# VOLTAJE.net
KiCad netlist of a schematic drawn in Altium Designer
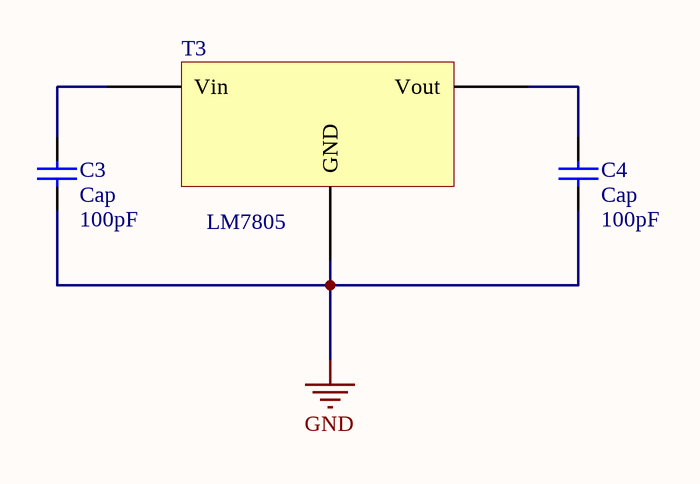
[diagram p0: VOLTAJE.SchDoc]

(export (version "E")
  (design (tool "Eeschema 10.0.6"))
  (components
    (comp (ref "C3")
      (value "Cap")
      (footprint "RAD-0.3")
      (description "Capacitor Ceramico")
      (fields
        (field (name "MANUFACTURER") "KEMET")
        (field (name "MANUFACTURER PART NUMBER") "C0402C104K8PACTU")
        (field (name "ALTIUM_VALUE") "100pF")
        (field (name "PUBLISHER") "Altium Limited")
      )
      (libsource (lib "LIBRERIAPROYECTO") (part "Cap"))
    )
    (comp (ref "C4")
      (value "Cap")
      (footprint "RAD-0.3")
      (description "Capacitor Ceramico")
      (fields
        (field (name "MANUFACTURER") "KEMET")
        (field (name "MANUFACTURER PART NUMBER") "C0402C104K8PACTU")
        (field (name "ALTIUM_VALUE") "100pF")
        (field (name "PUBLISHER") "Altium Limited")
      )
      (libsource (lib "LIBRERIAPROYECTO") (part "Cap"))
    )
    (comp (ref "T3")
      (value "LM7805")
      (footprint "LM7805")
      (description "Voltage Regulator")
      (fields
        (field (name "MANUFACTURER") "ON Semiconductor / Fairchild")
        (field (name "MANUFACTURER PART NUMBER") "LM7805CT")
      )
      (libsource (lib "LIBRERIAPROYECTO") (part "LM7805"))
    )
  )
  (nets
    (net (code "1") (name "GND") (class "Default")
      (node (ref "C3") (pin "1") (pinfunction "1_1") (pintype "passive"))
      (node (ref "C4") (pin "1") (pinfunction "1_1") (pintype "passive"))
      (node (ref "T3") (pin "174") (pinfunction "GND_174") (pintype "passive"))
    )
    (net (code "2") (name "Net-(T3-Vin)") (class "Default")
      (node (ref "C3") (pin "2") (pinfunction "2_2") (pintype "passive"))
      (node (ref "T3") (pin "173") (pinfunction "Vin_173") (pintype "passive"))
    )
    (net (code "3") (name "Net-(T3-Vout)") (class "Default")
      (node (ref "C4") (pin "2") (pinfunction "2_2") (pintype "passive"))
      (node (ref "T3") (pin "175") (pinfunction "Vout_175") (pintype "passive"))
    )
  )
)
